# IO.net
KiCad netlist of a schematic drawn in Altium Designer
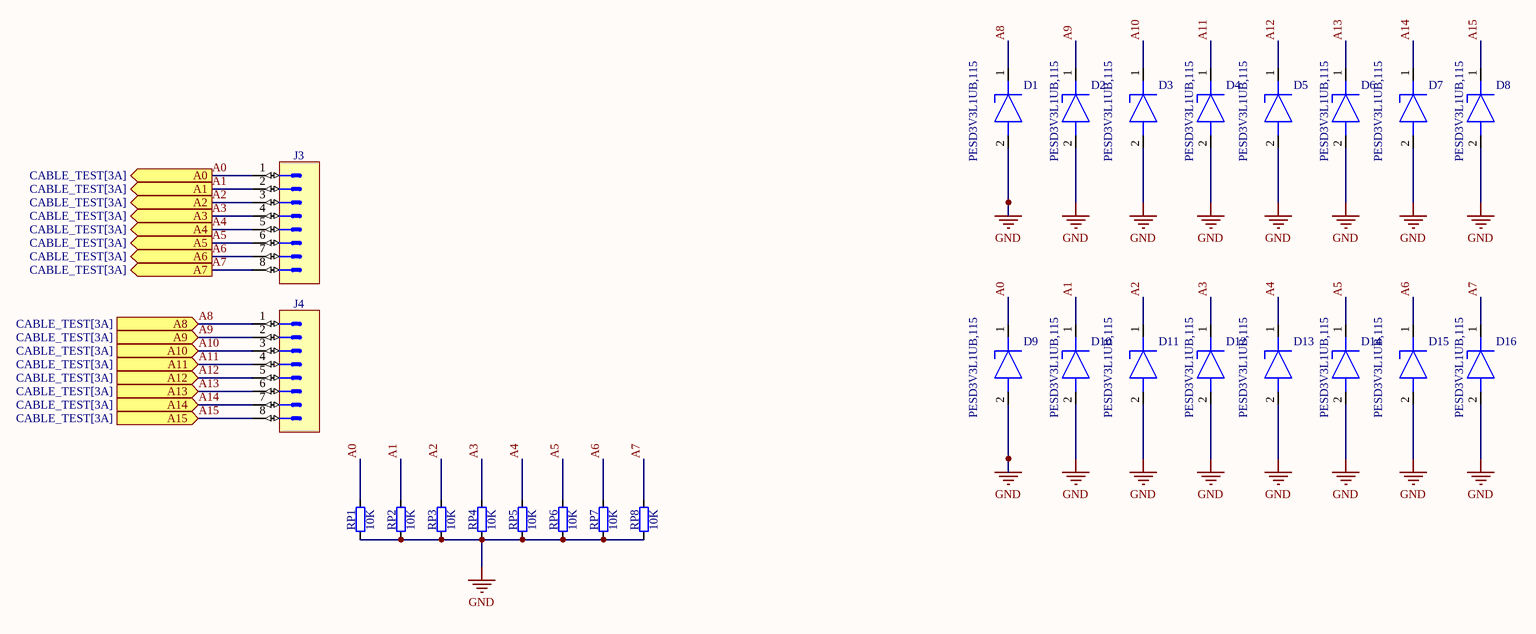
[diagram p0: IO.SchDoc]

(export (version "E")
  (design (tool "Eeschema 10.0.6"))
  (components
    (comp (ref "D1")
      (value "PESD3V3L1UB,115")
      (footprint "LORA:SODFL1608X65N")
      (description "Diode ESD (Uni-directional)")
      (fields (field (name "MOUSER PART NUMBER") "771-PESD3V3L1UB115"))
      (libsource (lib "*") (part "PESD3V3L1UB,115"))
    )
    (comp (ref "D2")
      (value "PESD3V3L1UB,115")
      (footprint "LORA:SODFL1608X65N")
      (description "Diode ESD (Uni-directional)")
      (fields (field (name "MOUSER PART NUMBER") "771-PESD3V3L1UB115"))
      (libsource (lib "*") (part "PESD3V3L1UB,115"))
    )
    (comp (ref "D3")
      (value "PESD3V3L1UB,115")
      (footprint "LORA:SODFL1608X65N")
      (description "Diode ESD (Uni-directional)")
      (fields (field (name "MOUSER PART NUMBER") "771-PESD3V3L1UB115"))
      (libsource (lib "*") (part "PESD3V3L1UB,115"))
    )
    (comp (ref "D4")
      (value "PESD3V3L1UB,115")
      (footprint "LORA:SODFL1608X65N")
      (description "Diode ESD (Uni-directional)")
      (fields (field (name "MOUSER PART NUMBER") "771-PESD3V3L1UB115"))
      (libsource (lib "*") (part "PESD3V3L1UB,115"))
    )
    (comp (ref "D5")
      (value "PESD3V3L1UB,115")
      (footprint "LORA:SODFL1608X65N")
      (description "Diode ESD (Uni-directional)")
      (fields (field (name "MOUSER PART NUMBER") "771-PESD3V3L1UB115"))
      (libsource (lib "*") (part "PESD3V3L1UB,115"))
    )
    (comp (ref "D6")
      (value "PESD3V3L1UB,115")
      (footprint "LORA:SODFL1608X65N")
      (description "Diode ESD (Uni-directional)")
      (fields (field (name "MOUSER PART NUMBER") "771-PESD3V3L1UB115"))
      (libsource (lib "*") (part "PESD3V3L1UB,115"))
    )
    (comp (ref "D7")
      (value "PESD3V3L1UB,115")
      (footprint "LORA:SODFL1608X65N")
      (description "Diode ESD (Uni-directional)")
      (fields (field (name "MOUSER PART NUMBER") "771-PESD3V3L1UB115"))
      (libsource (lib "*") (part "PESD3V3L1UB,115"))
    )
    (comp (ref "D8")
      (value "PESD3V3L1UB,115")
      (footprint "LORA:SODFL1608X65N")
      (description "Diode ESD (Uni-directional)")
      (fields (field (name "MOUSER PART NUMBER") "771-PESD3V3L1UB115"))
      (libsource (lib "*") (part "PESD3V3L1UB,115"))
    )
    (comp (ref "D9")
      (value "PESD3V3L1UB,115")
      (footprint "LORA:SODFL1608X65N")
      (description "Diode ESD (Uni-directional)")
      (fields (field (name "MOUSER PART NUMBER") "771-PESD3V3L1UB115"))
      (libsource (lib "*") (part "PESD3V3L1UB,115"))
    )
    (comp (ref "D10")
      (value "PESD3V3L1UB,115")
      (footprint "LORA:SODFL1608X65N")
      (description "Diode ESD (Uni-directional)")
      (fields (field (name "MOUSER PART NUMBER") "771-PESD3V3L1UB115"))
      (libsource (lib "*") (part "PESD3V3L1UB,115"))
    )
    (comp (ref "D11")
      (value "PESD3V3L1UB,115")
      (footprint "LORA:SODFL1608X65N")
      (description "Diode ESD (Uni-directional)")
      (fields (field (name "MOUSER PART NUMBER") "771-PESD3V3L1UB115"))
      (libsource (lib "*") (part "PESD3V3L1UB,115"))
    )
    (comp (ref "D12")
      (value "PESD3V3L1UB,115")
      (footprint "LORA:SODFL1608X65N")
      (description "Diode ESD (Uni-directional)")
      (fields (field (name "MOUSER PART NUMBER") "771-PESD3V3L1UB115"))
      (libsource (lib "*") (part "PESD3V3L1UB,115"))
    )
    (comp (ref "D13")
      (value "PESD3V3L1UB,115")
      (footprint "LORA:SODFL1608X65N")
      (description "Diode ESD (Uni-directional)")
      (fields (field (name "MOUSER PART NUMBER") "771-PESD3V3L1UB115"))
      (libsource (lib "*") (part "PESD3V3L1UB,115"))
    )
    (comp (ref "D14")
      (value "PESD3V3L1UB,115")
      (footprint "LORA:SODFL1608X65N")
      (description "Diode ESD (Uni-directional)")
      (fields (field (name "MOUSER PART NUMBER") "771-PESD3V3L1UB115"))
      (libsource (lib "*") (part "PESD3V3L1UB,115"))
    )
    (comp (ref "D15")
      (value "PESD3V3L1UB,115")
      (footprint "LORA:SODFL1608X65N")
      (description "Diode ESD (Uni-directional)")
      (fields (field (name "MOUSER PART NUMBER") "771-PESD3V3L1UB115"))
      (libsource (lib "*") (part "PESD3V3L1UB,115"))
    )
    (comp (ref "D16")
      (value "PESD3V3L1UB,115")
      (footprint "LORA:SODFL1608X65N")
      (description "Diode ESD (Uni-directional)")
      (fields (field (name "MOUSER PART NUMBER") "771-PESD3V3L1UB115"))
      (libsource (lib "*") (part "PESD3V3L1UB,115"))
    )
    (comp (ref "J3")
      (value "~")
      (footprint "PHOENIX_1757307")
      (description "Connector 8 Male")
      (fields
        (field (name "PART NUMBER") "PHOENIX_1757307")
        (field (name "MANUFACTURER") "PHOENIX CONTACT")
        (field (name "AUTHOR") "CERN DEM JLC")
      )
      (libsource (lib "Connectors") (part "Connector 8 Male"))
    )
    (comp (ref "J4")
      (value "~")
      (footprint "PHOENIX_1757307")
      (description "Connector 8 Male")
      (fields
        (field (name "PART NUMBER") "PHOENIX_1757307")
        (field (name "MANUFACTURER") "PHOENIX CONTACT")
        (field (name "AUTHOR") "CERN DEM JLC")
      )
      (libsource (lib "Connectors") (part "Connector 8 Male"))
    )
    (comp (ref "RP1")
      (value "10K")
      (footprint "RESC2012X60N")
      (description "Resistor - 1%")
      (fields
        (field (name "PART NUMBER") "R0805_24K_1%_0.125W_100PPM")
        (field (name "POWER") "0.125W")
        (field (name "AUTHOR") "CERN DEM JLC")
      )
      (libsource (lib "Resistors") (part "Resistor - 1%"))
    )
    (comp (ref "RP2")
      (value "10K")
      (footprint "RESC2012X60N")
      (description "Resistor - 1%")
      (fields
        (field (name "PART NUMBER") "R0805_24K_1%_0.125W_100PPM")
        (field (name "POWER") "0.125W")
        (field (name "AUTHOR") "CERN DEM JLC")
      )
      (libsource (lib "Resistors") (part "Resistor - 1%"))
    )
    (comp (ref "RP3")
      (value "10K")
      (footprint "RESC2012X60N")
      (description "Resistor - 1%")
      (fields
        (field (name "PART NUMBER") "R0805_24K_1%_0.125W_100PPM")
        (field (name "POWER") "0.125W")
        (field (name "AUTHOR") "CERN DEM JLC")
      )
      (libsource (lib "Resistors") (part "Resistor - 1%"))
    )
    (comp (ref "RP4")
      (value "10K")
      (footprint "RESC2012X60N")
      (description "Resistor - 1%")
      (fields
        (field (name "PART NUMBER") "R0805_24K_1%_0.125W_100PPM")
        (field (name "POWER") "0.125W")
        (field (name "AUTHOR") "CERN DEM JLC")
      )
      (libsource (lib "Resistors") (part "Resistor - 1%"))
    )
    (comp (ref "RP5")
      (value "10K")
      (footprint "RESC2012X60N")
      (description "Resistor - 1%")
      (fields
        (field (name "PART NUMBER") "R0805_24K_1%_0.125W_100PPM")
        (field (name "POWER") "0.125W")
        (field (name "AUTHOR") "CERN DEM JLC")
      )
      (libsource (lib "Resistors") (part "Resistor - 1%"))
    )
    (comp (ref "RP6")
      (value "10K")
      (footprint "RESC2012X60N")
      (description "Resistor - 1%")
      (fields
        (field (name "PART NUMBER") "R0805_24K_1%_0.125W_100PPM")
        (field (name "POWER") "0.125W")
        (field (name "AUTHOR") "CERN DEM JLC")
      )
      (libsource (lib "Resistors") (part "Resistor - 1%"))
    )
    (comp (ref "RP7")
      (value "10K")
      (footprint "RESC2012X60N")
      (description "Resistor - 1%")
      (fields
        (field (name "PART NUMBER") "R0805_24K_1%_0.125W_100PPM")
        (field (name "POWER") "0.125W")
        (field (name "AUTHOR") "CERN DEM JLC")
      )
      (libsource (lib "Resistors") (part "Resistor - 1%"))
    )
    (comp (ref "RP8")
      (value "10K")
      (footprint "RESC2012X60N")
      (description "Resistor - 1%")
      (fields
        (field (name "PART NUMBER") "R0805_24K_1%_0.125W_100PPM")
        (field (name "POWER") "0.125W")
        (field (name "AUTHOR") "CERN DEM JLC")
      )
      (libsource (lib "Resistors") (part "Resistor - 1%"))
    )
  )
  (nets
    (net (code "1") (name "/A0") (class "Default")
      (node (ref "D9") (pin "1") (pinfunction "K_1") (pintype "passive"))
      (node (ref "J3") (pin "1") (pinfunction "1_1") (pintype "bidirectional"))
      (node (ref "RP1") (pin "2") (pinfunction "2_2") (pintype "passive"))
    )
    (net (code "2") (name "/A1") (class "Default")
      (node (ref "D10") (pin "1") (pinfunction "K_1") (pintype "passive"))
      (node (ref "J3") (pin "2") (pinfunction "2_2") (pintype "bidirectional"))
      (node (ref "RP2") (pin "2") (pinfunction "2_2") (pintype "passive"))
    )
    (net (code "3") (name "/A2") (class "Default")
      (node (ref "D11") (pin "1") (pinfunction "K_1") (pintype "passive"))
      (node (ref "J3") (pin "3") (pinfunction "3_3") (pintype "bidirectional"))
      (node (ref "RP3") (pin "2") (pinfunction "2_2") (pintype "passive"))
    )
    (net (code "4") (name "/A3") (class "Default")
      (node (ref "D12") (pin "1") (pinfunction "K_1") (pintype "passive"))
      (node (ref "J3") (pin "4") (pinfunction "4_4") (pintype "bidirectional"))
      (node (ref "RP4") (pin "2") (pinfunction "2_2") (pintype "passive"))
    )
    (net (code "5") (name "/A4") (class "Default")
      (node (ref "D13") (pin "1") (pinfunction "K_1") (pintype "passive"))
      (node (ref "J3") (pin "5") (pinfunction "5_5") (pintype "bidirectional"))
      (node (ref "RP5") (pin "2") (pinfunction "2_2") (pintype "passive"))
    )
    (net (code "6") (name "/A5") (class "Default")
      (node (ref "D14") (pin "1") (pinfunction "K_1") (pintype "passive"))
      (node (ref "J3") (pin "6") (pinfunction "6_6") (pintype "bidirectional"))
      (node (ref "RP6") (pin "2") (pinfunction "2_2") (pintype "passive"))
    )
    (net (code "7") (name "/A6") (class "Default")
      (node (ref "D15") (pin "1") (pinfunction "K_1") (pintype "passive"))
      (node (ref "J3") (pin "7") (pinfunction "7_7") (pintype "bidirectional"))
      (node (ref "RP7") (pin "2") (pinfunction "2_2") (pintype "passive"))
    )
    (net (code "8") (name "/A7") (class "Default")
      (node (ref "D16") (pin "1") (pinfunction "K_1") (pintype "passive"))
      (node (ref "J3") (pin "8") (pinfunction "8_8") (pintype "bidirectional"))
      (node (ref "RP8") (pin "2") (pinfunction "2_2") (pintype "passive"))
    )
    (net (code "9") (name "/A8") (class "Default")
      (node (ref "D1") (pin "1") (pinfunction "K_1") (pintype "passive"))
      (node (ref "J4") (pin "1") (pinfunction "1_1") (pintype "bidirectional"))
    )
    (net (code "10") (name "/A9") (class "Default")
      (node (ref "D2") (pin "1") (pinfunction "K_1") (pintype "passive"))
      (node (ref "J4") (pin "2") (pinfunction "2_2") (pintype "bidirectional"))
    )
    (net (code "11") (name "/A10") (class "Default")
      (node (ref "D3") (pin "1") (pinfunction "K_1") (pintype "passive"))
      (node (ref "J4") (pin "3") (pinfunction "3_3") (pintype "bidirectional"))
    )
    (net (code "12") (name "/A11") (class "Default")
      (node (ref "D4") (pin "1") (pinfunction "K_1") (pintype "passive"))
      (node (ref "J4") (pin "4") (pinfunction "4_4") (pintype "bidirectional"))
    )
    (net (code "13") (name "/A12") (class "Default")
      (node (ref "D5") (pin "1") (pinfunction "K_1") (pintype "passive"))
      (node (ref "J4") (pin "5") (pinfunction "5_5") (pintype "bidirectional"))
    )
    (net (code "14") (name "/A13") (class "Default")
      (node (ref "D6") (pin "1") (pinfunction "K_1") (pintype "passive"))
      (node (ref "J4") (pin "6") (pinfunction "6_6") (pintype "bidirectional"))
    )
    (net (code "15") (name "/A14") (class "Default")
      (node (ref "D7") (pin "1") (pinfunction "K_1") (pintype "passive"))
      (node (ref "J4") (pin "7") (pinfunction "7_7") (pintype "bidirectional"))
    )
    (net (code "16") (name "/A15") (class "Default")
      (node (ref "D8") (pin "1") (pinfunction "K_1") (pintype "passive"))
      (node (ref "J4") (pin "8") (pinfunction "8_8") (pintype "bidirectional"))
    )
    (net (code "17") (name "GND") (class "Default")
      (node (ref "D1") (pin "2") (pinfunction "A_2") (pintype "passive"))
      (node (ref "D10") (pin "2") (pinfunction "A_2") (pintype "passive"))
      (node (ref "D11") (pin "2") (pinfunction "A_2") (pintype "passive"))
      (node (ref "D12") (pin "2") (pinfunction "A_2") (pintype "passive"))
      (node (ref "D13") (pin "2") (pinfunction "A_2") (pintype "passive"))
      (node (ref "D14") (pin "2") (pinfunction "A_2") (pintype "passive"))
      (node (ref "D15") (pin "2") (pinfunction "A_2") (pintype "passive"))
      (node (ref "D16") (pin "2") (pinfunction "A_2") (pintype "passive"))
      (node (ref "D2") (pin "2") (pinfunction "A_2") (pintype "passive"))
      (node (ref "D3") (pin "2") (pinfunction "A_2") (pintype "passive"))
      (node (ref "D4") (pin "2") (pinfunction "A_2") (pintype "passive"))
      (node (ref "D5") (pin "2") (pinfunction "A_2") (pintype "passive"))
      (node (ref "D6") (pin "2") (pinfunction "A_2") (pintype "passive"))
      (node (ref "D7") (pin "2") (pinfunction "A_2") (pintype "passive"))
      (node (ref "D8") (pin "2") (pinfunction "A_2") (pintype "passive"))
      (node (ref "D9") (pin "2") (pinfunction "A_2") (pintype "passive"))
      (node (ref "RP1") (pin "1") (pinfunction "1_1") (pintype "passive"))
      (node (ref "RP2") (pin "1") (pinfunction "1_1") (pintype "passive"))
      (node (ref "RP3") (pin "1") (pinfunction "1_1") (pintype "passive"))
      (node (ref "RP4") (pin "1") (pinfunction "1_1") (pintype "passive"))
      (node (ref "RP5") (pin "1") (pinfunction "1_1") (pintype "passive"))
      (node (ref "RP6") (pin "1") (pinfunction "1_1") (pintype "passive"))
      (node (ref "RP7") (pin "1") (pinfunction "1_1") (pintype "passive"))
      (node (ref "RP8") (pin "1") (pinfunction "1_1") (pintype "passive"))
    )
  )
)
